# amp.net
KiCad netlist of a schematic drawn in EAGLE
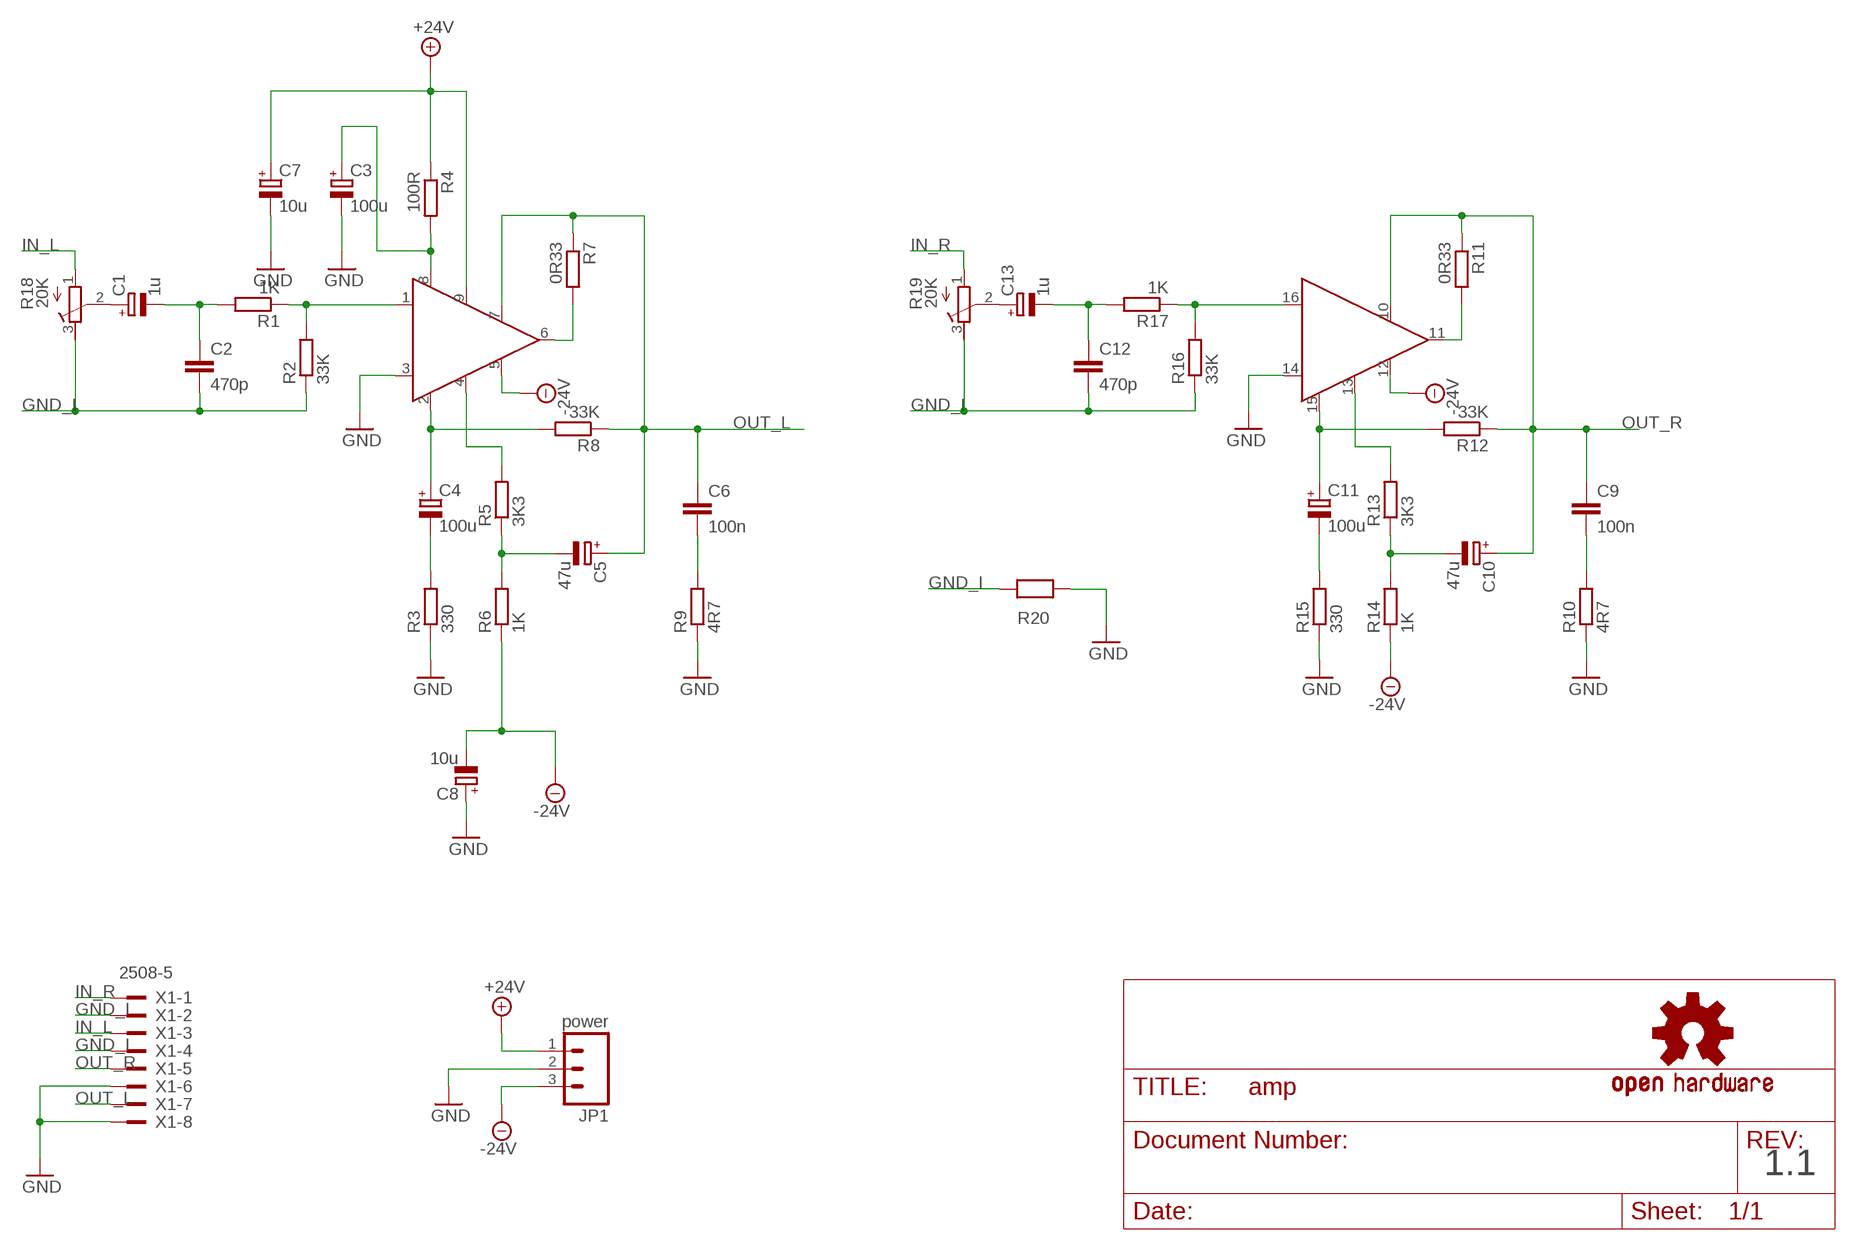
[diagram p0: schematic, sheet 1]

(export (version "E")
  (design (tool "Eeschema 10.0.6"))
  (components
    (comp (ref "C1")
      (value "1u")
      (footprint "eagle-import:PANASONIC_B")
      (libsource (lib "eagle-import") (part "CPOL-EUB"))
    )
    (comp (ref "C2")
      (value "470p")
      (footprint "eagle-import:C0805")
      (libsource (lib "eagle-import") (part "C-EUC0805"))
    )
    (comp (ref "C3")
      (value "100u")
      (footprint "eagle-import:PANASONIC_G")
      (libsource (lib "eagle-import") (part "CPOL-EUG"))
    )
    (comp (ref "C4")
      (value "100u")
      (footprint "eagle-import:PANASONIC_G")
      (libsource (lib "eagle-import") (part "CPOL-EUG"))
    )
    (comp (ref "C5")
      (value "47u")
      (footprint "eagle-import:PANASONIC_F")
      (libsource (lib "eagle-import") (part "CPOL-EUF"))
    )
    (comp (ref "C6")
      (value "100n")
      (footprint "eagle-import:C10B5")
      (libsource (lib "eagle-import") (part "C10/5"))
    )
    (comp (ref "C7")
      (value "10u")
      (footprint "eagle-import:PANASONIC_D")
      (libsource (lib "eagle-import") (part "CPOL-EUD"))
    )
    (comp (ref "C8")
      (value "10u")
      (footprint "eagle-import:PANASONIC_D")
      (libsource (lib "eagle-import") (part "CPOL-EUD"))
    )
    (comp (ref "C9")
      (value "100n")
      (footprint "eagle-import:C10B5")
      (libsource (lib "eagle-import") (part "C10/5"))
    )
    (comp (ref "C10")
      (value "47u")
      (footprint "eagle-import:PANASONIC_F")
      (libsource (lib "eagle-import") (part "CPOL-EUF"))
    )
    (comp (ref "C11")
      (value "100u")
      (footprint "eagle-import:PANASONIC_G")
      (libsource (lib "eagle-import") (part "CPOL-EUG"))
    )
    (comp (ref "C12")
      (value "470p")
      (footprint "eagle-import:C0805")
      (libsource (lib "eagle-import") (part "C-EUC0805"))
    )
    (comp (ref "C13")
      (value "1u")
      (footprint "eagle-import:PANASONIC_B")
      (libsource (lib "eagle-import") (part "CPOL-EUB"))
    )
    (comp (ref "JP1")
      (value "power")
      (footprint "eagle-import:1X03")
      (libsource (lib "eagle-import") (part "M03PTH"))
    )
    (comp (ref "R1")
      (value "1K")
      (footprint "eagle-import:R0805W")
      (libsource (lib "eagle-import") (part "R-EU_R0805W"))
    )
    (comp (ref "R2")
      (value "33K")
      (footprint "eagle-import:R0805W")
      (libsource (lib "eagle-import") (part "R-EU_R0805W"))
    )
    (comp (ref "R3")
      (value "330")
      (footprint "eagle-import:P0613_15")
      (libsource (lib "eagle-import") (part "R-EU_0613/15"))
    )
    (comp (ref "R4")
      (value "100R")
      (footprint "eagle-import:P0613_15")
      (libsource (lib "eagle-import") (part "R-EU_0613/15"))
    )
    (comp (ref "R5")
      (value "3K3")
      (footprint "eagle-import:P0613_15")
      (libsource (lib "eagle-import") (part "R-EU_0613/15"))
    )
    (comp (ref "R6")
      (value "1K")
      (footprint "eagle-import:P0613_15")
      (libsource (lib "eagle-import") (part "R-EU_0613/15"))
    )
    (comp (ref "R7")
      (value "0R33")
      (footprint "eagle-import:P0613_15")
      (libsource (lib "eagle-import") (part "R-EU_0613/15"))
    )
    (comp (ref "R8")
      (value "33K")
      (footprint "eagle-import:P0613_15")
      (libsource (lib "eagle-import") (part "R-EU_0613/15"))
    )
    (comp (ref "R9")
      (value "4R7")
      (footprint "eagle-import:P0613_15")
      (libsource (lib "eagle-import") (part "R-EU_0613/15"))
    )
    (comp (ref "R10")
      (value "4R7")
      (footprint "eagle-import:P0613_15")
      (libsource (lib "eagle-import") (part "R-EU_0613/15"))
    )
    (comp (ref "R11")
      (value "0R33")
      (footprint "eagle-import:P0613_15")
      (libsource (lib "eagle-import") (part "R-EU_0613/15"))
    )
    (comp (ref "R12")
      (value "33K")
      (footprint "eagle-import:P0613_15")
      (libsource (lib "eagle-import") (part "R-EU_0613/15"))
    )
    (comp (ref "R13")
      (value "3K3")
      (footprint "eagle-import:P0613_15")
      (libsource (lib "eagle-import") (part "R-EU_0613/15"))
    )
    (comp (ref "R14")
      (value "1K")
      (footprint "eagle-import:P0613_15")
      (libsource (lib "eagle-import") (part "R-EU_0613/15"))
    )
    (comp (ref "R15")
      (value "330")
      (footprint "eagle-import:P0613_15")
      (libsource (lib "eagle-import") (part "R-EU_0613/15"))
    )
    (comp (ref "R16")
      (value "33K")
      (footprint "eagle-import:R0805W")
      (libsource (lib "eagle-import") (part "R-EU_R0805W"))
    )
    (comp (ref "R17")
      (value "1K")
      (footprint "eagle-import:R0805W")
      (libsource (lib "eagle-import") (part "R-EU_R0805W"))
    )
    (comp (ref "R18")
      (value "20K")
      (footprint "eagle-import:RTRIM3339P")
      (libsource (lib "eagle-import") (part "R-TRIMM3339P"))
    )
    (comp (ref "R19")
      (value "20K")
      (footprint "eagle-import:RTRIM3339P")
      (libsource (lib "eagle-import") (part "R-TRIMM3339P"))
    )
    (comp (ref "R20")
      (value "0R_0805")
      (footprint "eagle-import:R0805W")
      (libsource (lib "eagle-import") (part "0R_0805"))
    )
    (comp (ref "U$1")
      (value "STK465HORIZ-BOTTOM")
      (footprint "eagle-import:STK465-HB")
      (libsource (lib "eagle-import") (part "STK465HORIZ-BOTTOM"))
    )
    (comp (ref "U$7")
      (value "OSHW-LOGOM")
      (footprint "eagle-import:OSHW-LOGO-M")
      (libsource (lib "eagle-import") (part "OSHW-LOGOM"))
    )
    (comp (ref "X1")
      (value "2508-5")
      (footprint "eagle-import:PAK100_2500-5-08")
      (libsource (lib "eagle-import") (part "2508-5"))
    )
  )
  (nets
    (net (code "1") (name "+24V") (class "Default")
      (node (ref "C7") (pin "+") (pinfunction "+_+") (pintype "passive"))
      (node (ref "JP1") (pin "1") (pinfunction "1_1") (pintype "passive"))
      (node (ref "R4") (pin "1") (pinfunction "1_1") (pintype "passive"))
      (node (ref "U$1") (pin "9") (pinfunction "9_9") (pintype "bidirectional"))
    )
    (net (code "2") (name "-24V") (class "Default")
      (node (ref "C8") (pin "-") (pinfunction "-_-") (pintype "passive"))
      (node (ref "JP1") (pin "3") (pinfunction "3_3") (pintype "passive"))
      (node (ref "R14") (pin "1") (pinfunction "1_1") (pintype "passive"))
      (node (ref "R6") (pin "1") (pinfunction "1_1") (pintype "passive"))
      (node (ref "U$1") (pin "12") (pinfunction "12_12") (pintype "bidirectional"))
      (node (ref "U$1") (pin "5") (pinfunction "5_5") (pintype "bidirectional"))
    )
    (net (code "3") (name "/GND_I") (class "Default")
      (node (ref "C12") (pin "2") (pinfunction "2_2") (pintype "passive"))
      (node (ref "C2") (pin "2") (pinfunction "2_2") (pintype "passive"))
      (node (ref "R16") (pin "1") (pinfunction "1_1") (pintype "passive"))
      (node (ref "R18") (pin "3") (pinfunction "E_3") (pintype "passive"))
      (node (ref "R19") (pin "3") (pinfunction "E_3") (pintype "passive"))
      (node (ref "R2") (pin "1") (pinfunction "1_1") (pintype "passive"))
      (node (ref "R20") (pin "1") (pinfunction "P$1_1") (pintype "bidirectional"))
      (node (ref "X1") (pin "2") (pinfunction "KL_2") (pintype "passive"))
      (node (ref "X1") (pin "4") (pinfunction "KL_4") (pintype "passive"))
    )
    (net (code "4") (name "/IN_L") (class "Default")
      (node (ref "R18") (pin "1") (pinfunction "A_1") (pintype "passive"))
      (node (ref "X1") (pin "3") (pinfunction "KL_3") (pintype "passive"))
    )
    (net (code "5") (name "/IN_R") (class "Default")
      (node (ref "R19") (pin "1") (pinfunction "A_1") (pintype "passive"))
      (node (ref "X1") (pin "1") (pinfunction "KL_1") (pintype "passive"))
    )
    (net (code "6") (name "/OUT_L") (class "Default")
      (node (ref "C5") (pin "+") (pinfunction "+_+") (pintype "passive"))
      (node (ref "C6") (pin "1") (pinfunction "1_1") (pintype "passive"))
      (node (ref "R7") (pin "1") (pinfunction "1_1") (pintype "passive"))
      (node (ref "R8") (pin "1") (pinfunction "1_1") (pintype "passive"))
      (node (ref "U$1") (pin "7") (pinfunction "7_7") (pintype "bidirectional"))
      (node (ref "X1") (pin "7") (pinfunction "KL_7") (pintype "passive"))
    )
    (net (code "7") (name "/OUT_R") (class "Default")
      (node (ref "C10") (pin "+") (pinfunction "+_+") (pintype "passive"))
      (node (ref "C9") (pin "1") (pinfunction "1_1") (pintype "passive"))
      (node (ref "R11") (pin "1") (pinfunction "1_1") (pintype "passive"))
      (node (ref "R12") (pin "1") (pinfunction "1_1") (pintype "passive"))
      (node (ref "U$1") (pin "10") (pinfunction "10_10") (pintype "bidirectional"))
      (node (ref "X1") (pin "5") (pinfunction "KL_5") (pintype "passive"))
    )
    (net (code "8") (name "GND") (class "Default")
      (node (ref "C3") (pin "-") (pinfunction "-_-") (pintype "passive"))
      (node (ref "C7") (pin "-") (pinfunction "-_-") (pintype "passive"))
      (node (ref "C8") (pin "+") (pinfunction "+_+") (pintype "passive"))
      (node (ref "JP1") (pin "2") (pinfunction "2_2") (pintype "passive"))
      (node (ref "R10") (pin "1") (pinfunction "1_1") (pintype "passive"))
      (node (ref "R15") (pin "1") (pinfunction "1_1") (pintype "passive"))
      (node (ref "R20") (pin "2") (pinfunction "P$2_2") (pintype "bidirectional"))
      (node (ref "R3") (pin "1") (pinfunction "1_1") (pintype "passive"))
      (node (ref "R9") (pin "1") (pinfunction "1_1") (pintype "passive"))
      (node (ref "U$1") (pin "14") (pinfunction "14_14") (pintype "bidirectional"))
      (node (ref "U$1") (pin "3") (pinfunction "3_3") (pintype "bidirectional"))
      (node (ref "X1") (pin "6") (pinfunction "KL_6") (pintype "passive"))
      (node (ref "X1") (pin "8") (pinfunction "KL_8") (pintype "passive"))
    )
    (net (code "9") (name "Net-(C1-Pad-)") (class "Default")
      (node (ref "C1") (pin "-") (pinfunction "-_-") (pintype "passive"))
      (node (ref "C2") (pin "1") (pinfunction "1_1") (pintype "passive"))
      (node (ref "R1") (pin "2") (pinfunction "2_2") (pintype "passive"))
    )
    (net (code "10") (name "Net-(C3-Pad+)") (class "Default")
      (node (ref "C3") (pin "+") (pinfunction "+_+") (pintype "passive"))
      (node (ref "R4") (pin "2") (pinfunction "2_2") (pintype "passive"))
      (node (ref "U$1") (pin "8") (pinfunction "8_8") (pintype "bidirectional"))
    )
    (net (code "11") (name "Net-(C4-Pad+)") (class "Default")
      (node (ref "C4") (pin "+") (pinfunction "+_+") (pintype "passive"))
      (node (ref "R8") (pin "2") (pinfunction "2_2") (pintype "passive"))
      (node (ref "U$1") (pin "2") (pinfunction "2_2") (pintype "bidirectional"))
    )
    (net (code "12") (name "Net-(C4-Pad-)") (class "Default")
      (node (ref "C4") (pin "-") (pinfunction "-_-") (pintype "passive"))
      (node (ref "R3") (pin "2") (pinfunction "2_2") (pintype "passive"))
    )
    (net (code "13") (name "Net-(C5-Pad-)") (class "Default")
      (node (ref "C5") (pin "-") (pinfunction "-_-") (pintype "passive"))
      (node (ref "R5") (pin "1") (pinfunction "1_1") (pintype "passive"))
      (node (ref "R6") (pin "2") (pinfunction "2_2") (pintype "passive"))
    )
    (net (code "14") (name "Net-(C6-Pad2)") (class "Default")
      (node (ref "C6") (pin "2") (pinfunction "2_2") (pintype "passive"))
      (node (ref "R9") (pin "2") (pinfunction "2_2") (pintype "passive"))
    )
    (net (code "15") (name "Net-(C9-Pad2)") (class "Default")
      (node (ref "C9") (pin "2") (pinfunction "2_2") (pintype "passive"))
      (node (ref "R10") (pin "2") (pinfunction "2_2") (pintype "passive"))
    )
    (net (code "16") (name "Net-(C10-Pad-)") (class "Default")
      (node (ref "C10") (pin "-") (pinfunction "-_-") (pintype "passive"))
      (node (ref "R13") (pin "1") (pinfunction "1_1") (pintype "passive"))
      (node (ref "R14") (pin "2") (pinfunction "2_2") (pintype "passive"))
    )
    (net (code "17") (name "Net-(C11-Pad+)") (class "Default")
      (node (ref "C11") (pin "+") (pinfunction "+_+") (pintype "passive"))
      (node (ref "R12") (pin "2") (pinfunction "2_2") (pintype "passive"))
      (node (ref "U$1") (pin "15") (pinfunction "15_15") (pintype "bidirectional"))
    )
    (net (code "18") (name "Net-(C11-Pad-)") (class "Default")
      (node (ref "C11") (pin "-") (pinfunction "-_-") (pintype "passive"))
      (node (ref "R15") (pin "2") (pinfunction "2_2") (pintype "passive"))
    )
    (net (code "19") (name "Net-(C12-Pad1)") (class "Default")
      (node (ref "C12") (pin "1") (pinfunction "1_1") (pintype "passive"))
      (node (ref "C13") (pin "-") (pinfunction "-_-") (pintype "passive"))
      (node (ref "R17") (pin "2") (pinfunction "2_2") (pintype "passive"))
    )
    (net (code "20") (name "Net-(R1-Pad1)") (class "Default")
      (node (ref "R1") (pin "1") (pinfunction "1_1") (pintype "passive"))
      (node (ref "R2") (pin "2") (pinfunction "2_2") (pintype "passive"))
      (node (ref "U$1") (pin "1") (pinfunction "1_1") (pintype "bidirectional"))
    )
    (net (code "21") (name "Net-(R5-Pad2)") (class "Default")
      (node (ref "R5") (pin "2") (pinfunction "2_2") (pintype "passive"))
      (node (ref "U$1") (pin "4") (pinfunction "4_4") (pintype "bidirectional"))
    )
    (net (code "22") (name "Net-(R7-Pad2)") (class "Default")
      (node (ref "R7") (pin "2") (pinfunction "2_2") (pintype "passive"))
      (node (ref "U$1") (pin "6") (pinfunction "6_6") (pintype "bidirectional"))
    )
    (net (code "23") (name "Net-(R11-Pad2)") (class "Default")
      (node (ref "R11") (pin "2") (pinfunction "2_2") (pintype "passive"))
      (node (ref "U$1") (pin "11") (pinfunction "11_11") (pintype "bidirectional"))
    )
    (net (code "24") (name "Net-(R13-Pad2)") (class "Default")
      (node (ref "R13") (pin "2") (pinfunction "2_2") (pintype "passive"))
      (node (ref "U$1") (pin "13") (pinfunction "13_13") (pintype "bidirectional"))
    )
    (net (code "25") (name "Net-(R16-Pad2)") (class "Default")
      (node (ref "R16") (pin "2") (pinfunction "2_2") (pintype "passive"))
      (node (ref "R17") (pin "1") (pinfunction "1_1") (pintype "passive"))
      (node (ref "U$1") (pin "16") (pinfunction "16_16") (pintype "bidirectional"))
    )
    (net (code "26") (name "Net-(R18-S)") (class "Default")
      (node (ref "C1") (pin "+") (pinfunction "+_+") (pintype "passive"))
      (node (ref "R18") (pin "2") (pinfunction "S_2") (pintype "passive"))
    )
    (net (code "27") (name "Net-(R19-S)") (class "Default")
      (node (ref "C13") (pin "+") (pinfunction "+_+") (pintype "passive"))
      (node (ref "R19") (pin "2") (pinfunction "S_2") (pintype "passive"))
    )
  )
)
